# fabisp.net
KiCad netlist of a schematic drawn in EAGLE
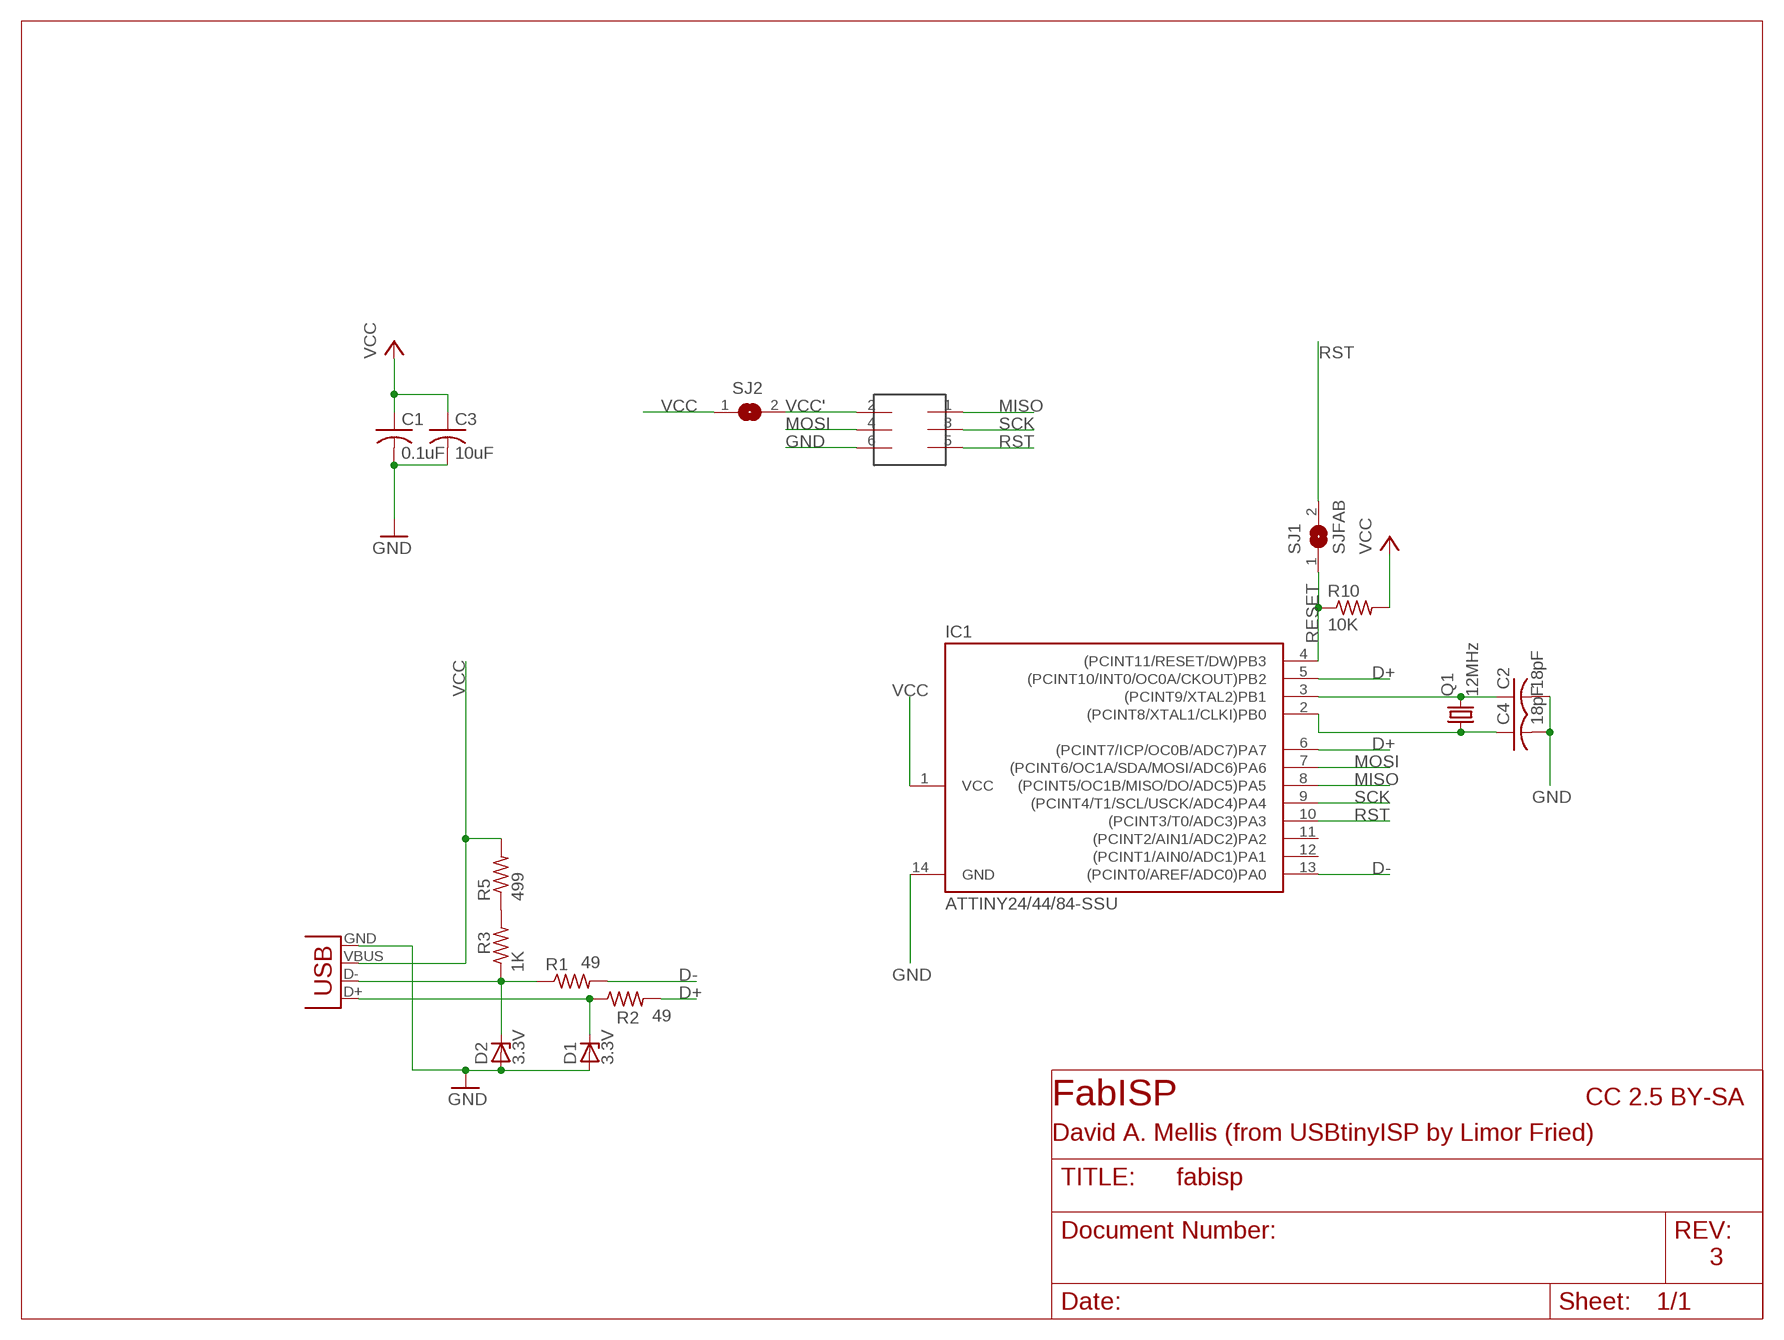
[diagram p0: schematic, sheet 1]

(export (version "E")
  (design (tool "Eeschema 10.0.6"))
  (components
    (comp (ref "C1")
      (value "0.1uF")
      (footprint "eagle-import:C1206")
      (libsource (lib "eagle-import") (part "rcl-ez_C-USC1206"))
    )
    (comp (ref "C2")
      (value "18pF")
      (footprint "eagle-import:C1206")
      (libsource (lib "eagle-import") (part "C-USC1206"))
    )
    (comp (ref "C3")
      (value "10uF")
      (footprint "eagle-import:C1206")
      (libsource (lib "eagle-import") (part "C-USC1206"))
    )
    (comp (ref "C4")
      (value "18pF")
      (footprint "eagle-import:C1206")
      (libsource (lib "eagle-import") (part "C-USC1206"))
    )
    (comp (ref "D1")
      (value "3.3V")
      (footprint "eagle-import:SOD123")
      (libsource (lib "eagle-import") (part "ZENER_DIODESOD123"))
    )
    (comp (ref "D2")
      (value "3.3V")
      (footprint "eagle-import:SOD123")
      (libsource (lib "eagle-import") (part "ZENER_DIODESOD123"))
    )
    (comp (ref "IC1")
      (value "ATTINY24/44/84-SSU")
      (footprint "eagle-import:SOIC14")
      (libsource (lib "eagle-import") (part "ATTINY24/44/84-SSU"))
    )
    (comp (ref "Q1")
      (value "12MHz")
      (footprint "eagle-import:HC49UP")
      (libsource (lib "eagle-import") (part "CRYSTALHC49UP"))
    )
    (comp (ref "R1")
      (value "49")
      (footprint "eagle-import:R1206")
      (libsource (lib "eagle-import") (part "rcl-ez_R-US_R1206"))
    )
    (comp (ref "R2")
      (value "49")
      (footprint "eagle-import:R1206")
      (libsource (lib "eagle-import") (part "rcl-ez_R-US_R1206"))
    )
    (comp (ref "R3")
      (value "1K")
      (footprint "eagle-import:R1206")
      (libsource (lib "eagle-import") (part "rcl-ez_R-US_R1206"))
    )
    (comp (ref "R5")
      (value "499")
      (footprint "eagle-import:R1206")
      (libsource (lib "eagle-import") (part "R-US_R1206"))
    )
    (comp (ref "R10")
      (value "10K")
      (footprint "eagle-import:R1206")
      (libsource (lib "eagle-import") (part "rcl-ez_R-US_R1206"))
    )
    (comp (ref "SJ1")
      (value "SJFAB")
      (footprint "eagle-import:SJFAB")
      (libsource (lib "eagle-import") (part "SJFAB"))
    )
    (comp (ref "SJ2")
      (value "SJFAB")
      (footprint "eagle-import:SJFAB")
      (libsource (lib "eagle-import") (part "SJFAB"))
    )
    (comp (ref "U$1")
      (value "2X3HEADER")
      (footprint "eagle-import:2X3_SMD")
      (libsource (lib "eagle-import") (part "2X3HEADER"))
    )
    (comp (ref "X1")
      (value "USB_MINIB")
      (footprint "eagle-import:USB_MINIB")
      (libsource (lib "eagle-import") (part "USB_MINIB"))
    )
  )
  (nets
    (net (code "1") (name "/D+") (class "Default")
      (node (ref "IC1") (pin "5") (pinfunction "(PCINT10/INT0/OC0A/CKOUT)PB2_5") (pintype "bidirectional"))
      (node (ref "IC1") (pin "6") (pinfunction "(PCINT7/ICP/OC0B/ADC7)PA7_6") (pintype "bidirectional"))
      (node (ref "R2") (pin "2") (pinfunction "2_2") (pintype "passive"))
    )
    (net (code "2") (name "/D-") (class "Default")
      (node (ref "IC1") (pin "13") (pinfunction "(PCINT0/AREF/ADC0)PA0_13") (pintype "bidirectional"))
      (node (ref "R1") (pin "2") (pinfunction "2_2") (pintype "passive"))
    )
    (net (code "3") (name "/MISO") (class "Default")
      (node (ref "IC1") (pin "8") (pinfunction "(PCINT5/OC1B/MISO/DO/ADC5)PA5_8") (pintype "bidirectional"))
      (node (ref "U$1") (pin "1") (pinfunction "P$1_1") (pintype "bidirectional"))
    )
    (net (code "4") (name "/MOSI") (class "Default")
      (node (ref "IC1") (pin "7") (pinfunction "(PCINT6/OC1A/SDA/MOSI/ADC6)PA6_7") (pintype "bidirectional"))
      (node (ref "U$1") (pin "4") (pinfunction "P$4_4") (pintype "bidirectional"))
    )
    (net (code "5") (name "/RESET") (class "Default")
      (node (ref "IC1") (pin "4") (pinfunction "(PCINT11/RESET/DW)PB3_4") (pintype "bidirectional"))
      (node (ref "R10") (pin "1") (pinfunction "1_1") (pintype "passive"))
      (node (ref "SJ1") (pin "1") (pinfunction "1_1") (pintype "passive"))
    )
    (net (code "6") (name "/RST") (class "Default")
      (node (ref "IC1") (pin "10") (pinfunction "(PCINT3/T0/ADC3)PA3_10") (pintype "bidirectional"))
      (node (ref "SJ1") (pin "2") (pinfunction "2_2") (pintype "passive"))
      (node (ref "U$1") (pin "5") (pinfunction "P$5_5") (pintype "bidirectional"))
    )
    (net (code "7") (name "/SCK") (class "Default")
      (node (ref "IC1") (pin "9") (pinfunction "(PCINT4/T1/SCL/USCK/ADC4)PA4_9") (pintype "bidirectional"))
      (node (ref "U$1") (pin "3") (pinfunction "P$3_3") (pintype "bidirectional"))
    )
    (net (code "8") (name "/VCC'") (class "Default")
      (node (ref "SJ2") (pin "2") (pinfunction "2_2") (pintype "passive"))
      (node (ref "U$1") (pin "2") (pinfunction "P$2_2") (pintype "bidirectional"))
    )
    (net (code "9") (name "GND") (class "Default")
      (node (ref "C1") (pin "2") (pinfunction "2_2") (pintype "passive"))
      (node (ref "C2") (pin "2") (pinfunction "2_2") (pintype "passive"))
      (node (ref "C3") (pin "2") (pinfunction "2_2") (pintype "passive"))
      (node (ref "C4") (pin "2") (pinfunction "2_2") (pintype "passive"))
      (node (ref "D1") (pin "ANODE") (pinfunction "ANODE_ANODE") (pintype "passive"))
      (node (ref "D2") (pin "ANODE") (pinfunction "ANODE_ANODE") (pintype "passive"))
      (node (ref "IC1") (pin "14") (pinfunction "GND_14") (pintype "power_in"))
      (node (ref "U$1") (pin "6") (pinfunction "P$6_6") (pintype "bidirectional"))
      (node (ref "X1") (pin "GND") (pinfunction "GND_GND") (pintype "bidirectional"))
    )
    (net (code "10") (name "Net-(D1-PadCATHODE)") (class "Default")
      (node (ref "D1") (pin "CATHODE") (pinfunction "CATHODE_CATHODE") (pintype "passive"))
      (node (ref "R2") (pin "1") (pinfunction "1_1") (pintype "passive"))
      (node (ref "X1") (pin "D+") (pinfunction "D+_D+") (pintype "bidirectional"))
    )
    (net (code "11") (name "Net-(D2-PadCATHODE)") (class "Default")
      (node (ref "D2") (pin "CATHODE") (pinfunction "CATHODE_CATHODE") (pintype "passive"))
      (node (ref "R1") (pin "1") (pinfunction "1_1") (pintype "passive"))
      (node (ref "R3") (pin "1") (pinfunction "1_1") (pintype "passive"))
      (node (ref "X1") (pin "D-") (pinfunction "D-_D-") (pintype "bidirectional"))
    )
    (net (code "12") (name "Net-(IC1-(PCINT8{slash}XTAL1{slash}CLKI)PB0)") (class "Default")
      (node (ref "C4") (pin "1") (pinfunction "1_1") (pintype "passive"))
      (node (ref "IC1") (pin "2") (pinfunction "(PCINT8/XTAL1/CLKI)PB0_2") (pintype "bidirectional"))
      (node (ref "Q1") (pin "1") (pinfunction "1_1") (pintype "passive"))
    )
    (net (code "13") (name "Net-(IC1-(PCINT9{slash}XTAL2)PB1)") (class "Default")
      (node (ref "C2") (pin "1") (pinfunction "1_1") (pintype "passive"))
      (node (ref "IC1") (pin "3") (pinfunction "(PCINT9/XTAL2)PB1_3") (pintype "bidirectional"))
      (node (ref "Q1") (pin "2") (pinfunction "2_2") (pintype "passive"))
    )
    (net (code "14") (name "Net-(R3-Pad2)") (class "Default")
      (node (ref "R3") (pin "2") (pinfunction "2_2") (pintype "passive"))
      (node (ref "R5") (pin "1") (pinfunction "1_1") (pintype "passive"))
    )
    (net (code "15") (name "VCC") (class "Default")
      (node (ref "C1") (pin "1") (pinfunction "1_1") (pintype "passive"))
      (node (ref "C3") (pin "1") (pinfunction "1_1") (pintype "passive"))
      (node (ref "IC1") (pin "1") (pinfunction "VCC_1") (pintype "power_in"))
      (node (ref "R10") (pin "2") (pinfunction "2_2") (pintype "passive"))
      (node (ref "R5") (pin "2") (pinfunction "2_2") (pintype "passive"))
      (node (ref "SJ2") (pin "1") (pinfunction "1_1") (pintype "passive"))
      (node (ref "X1") (pin "VBUS") (pinfunction "VBUS_VBUS") (pintype "bidirectional"))
    )
    (net (code "16") (name "unconnected-(IC1-(PCINT1{slash}AIN0{slash}ADC1)PA1-Pad12)") (class "Default")
      (node (ref "IC1") (pin "12") (pinfunction "(PCINT1/AIN0/ADC1)PA1_12") (pintype "bidirectional"))
    )
    (net (code "17") (name "unconnected-(IC1-(PCINT2{slash}AIN1{slash}ADC2)PA2-Pad11)") (class "Default")
      (node (ref "IC1") (pin "11") (pinfunction "(PCINT2/AIN1/ADC2)PA2_11") (pintype "bidirectional"))
    )
  )
)
